# smart_motor_controller.net
KiCad netlist of a schematic drawn in EAGLE
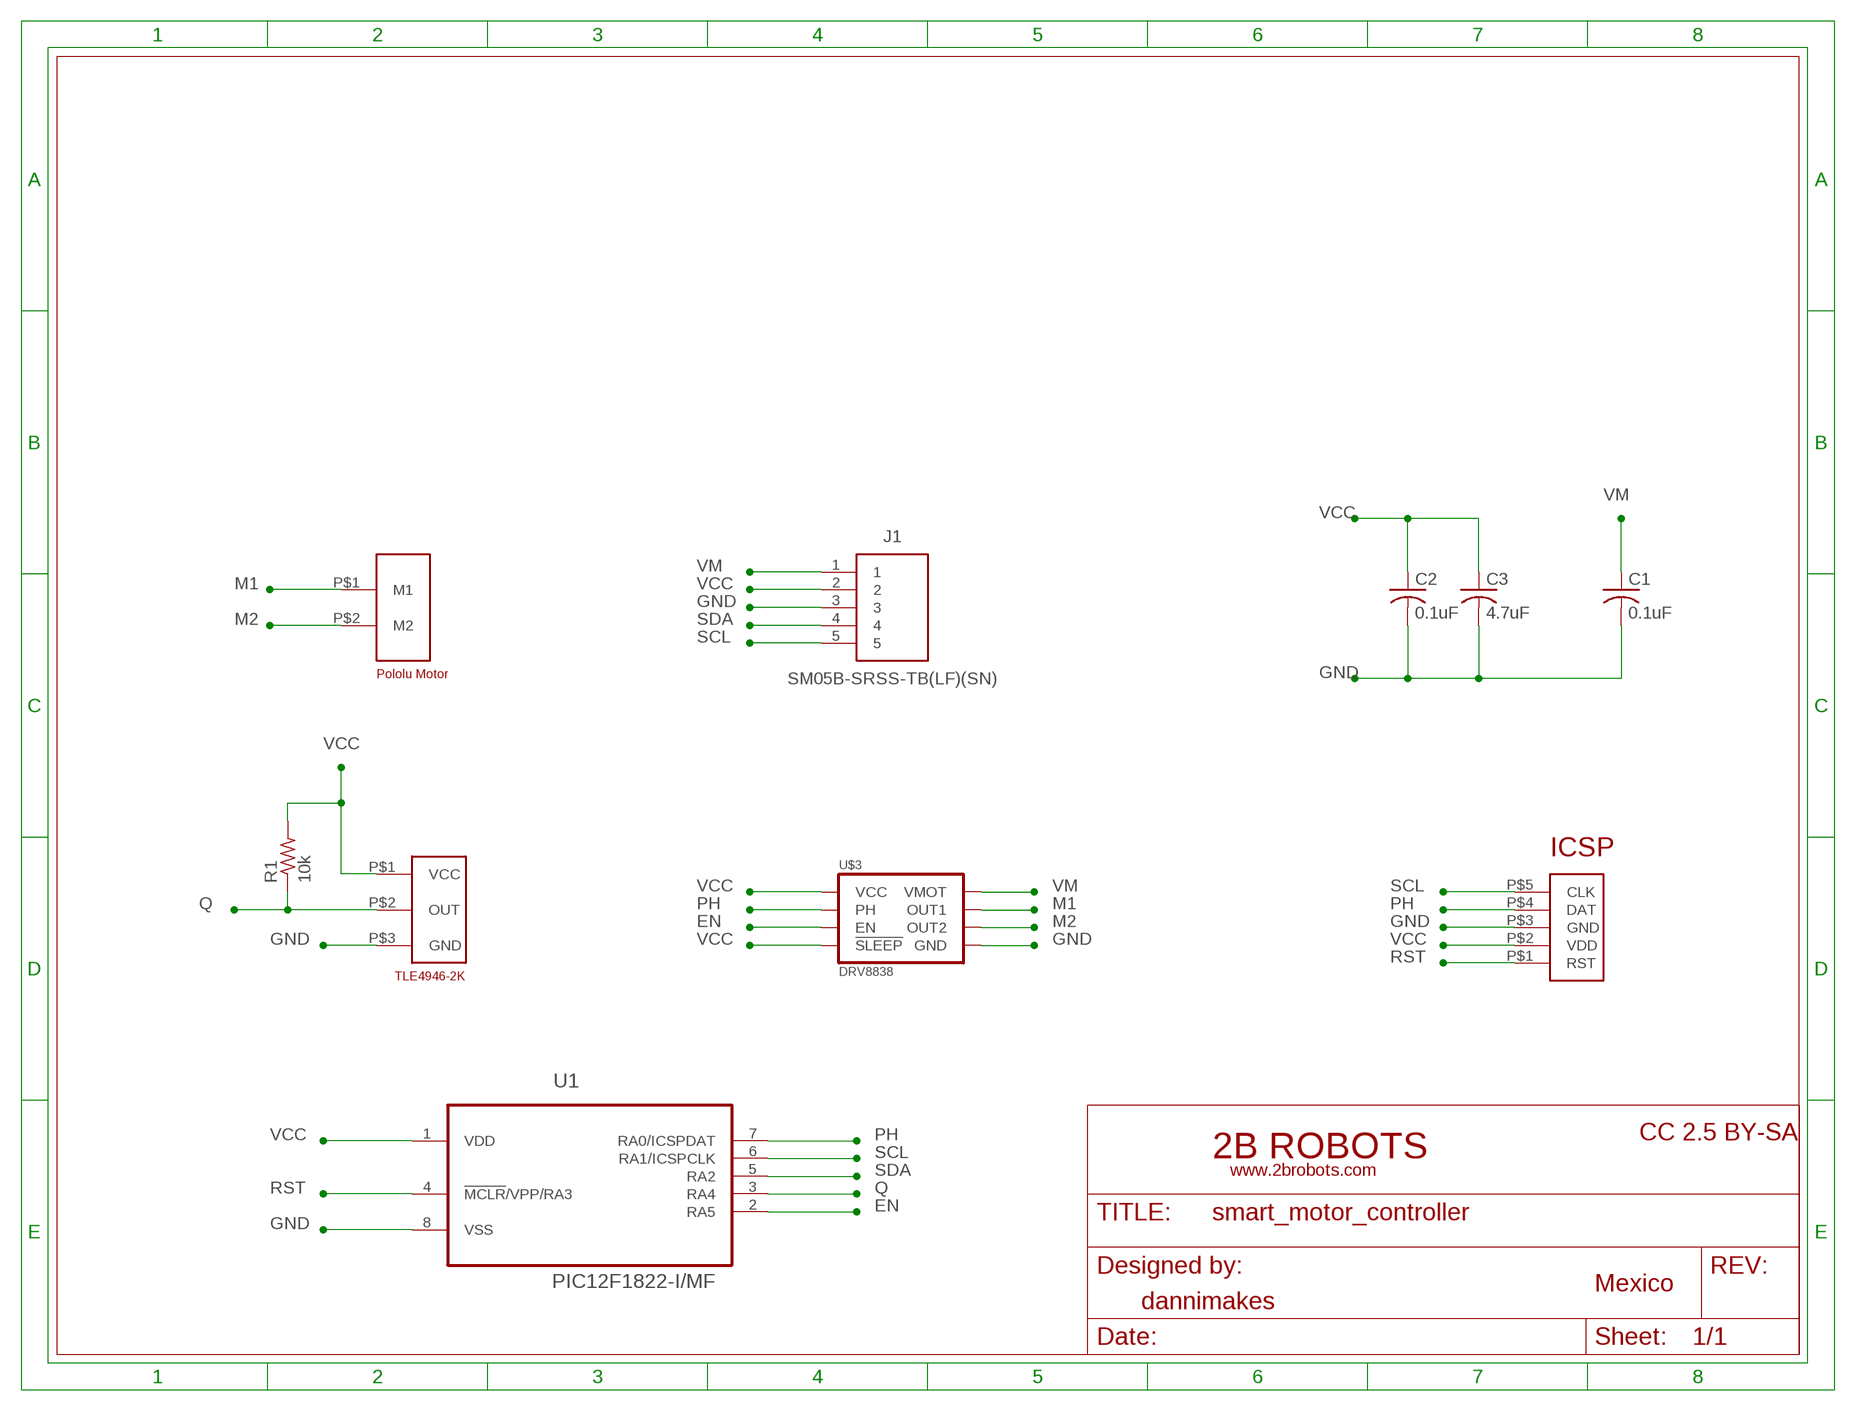
[diagram p0: schematic, sheet 1]

(export (version "E")
  (design (tool "Eeschema 10.0.6"))
  (components
    (comp (ref "C1")
      (value "0.1uF")
      (footprint "eagle-import:C0603K")
      (libsource (lib "eagle-import") (part "C-USC0603K"))
    )
    (comp (ref "C2")
      (value "0.1uF")
      (footprint "eagle-import:C0603K")
      (libsource (lib "eagle-import") (part "C-USC0603K"))
    )
    (comp (ref "C3")
      (value "4.7uF")
      (footprint "eagle-import:C0805K")
      (libsource (lib "eagle-import") (part "C-USC0805K"))
    )
    (comp (ref "J1")
      (value "SM05B-SRSS-TB(LF)(SN)")
      (footprint "eagle-import:SM05B-SRSS-TB(LF)(SN)")
      (libsource (lib "eagle-import") (part "SM05B-SRSS-TB(LF)(SN)"))
    )
    (comp (ref "R1")
      (value "10k")
      (footprint "eagle-import:R0805")
      (libsource (lib "eagle-import") (part "R-US_R0805"))
    )
    (comp (ref "U$1")
      (value "ICSP_POGO")
      (footprint "eagle-import:ICSP_POGO")
      (libsource (lib "eagle-import") (part "ICSP_POGO"))
    )
    (comp (ref "U$3")
      (value "DRV8838")
      (footprint "eagle-import:DSG")
      (libsource (lib "eagle-import") (part "DRV8838"))
    )
    (comp (ref "U$4")
      (value "TLE4946-2K")
      (footprint "eagle-import:SC59")
      (libsource (lib "eagle-import") (part "TLE4946-2K"))
    )
    (comp (ref "U$5")
      (value "POLOLU-MOTOR-BACK")
      (footprint "eagle-import:POLOL-MOTOR-BACK")
      (libsource (lib "eagle-import") (part "POLOLU-MOTOR-BACK"))
    )
    (comp (ref "U1")
      (value "PIC12F1822-I/MF")
      (footprint "eagle-import:DFN300X300X100-9N")
      (libsource (lib "eagle-import") (part "PIC12F1822-I/MF"))
    )
  )
  (nets
    (net (code "1") (name "/EN") (class "Default")
      (node (ref "U$3") (pin "5") (pinfunction "EN_5") (pintype "bidirectional"))
      (node (ref "U1") (pin "2") (pinfunction "RA5_2") (pintype "bidirectional"))
    )
    (net (code "2") (name "/GND") (class "Default")
      (node (ref "C1") (pin "2") (pinfunction "2_2") (pintype "passive"))
      (node (ref "C2") (pin "2") (pinfunction "2_2") (pintype "passive"))
      (node (ref "C3") (pin "2") (pinfunction "2_2") (pintype "passive"))
      (node (ref "J1") (pin "3") (pinfunction "3_3") (pintype "passive"))
      (node (ref "U$1") (pin "P$3") (pinfunction "GND_P$3") (pintype "bidirectional"))
      (node (ref "U$3") (pin "4") (pinfunction "GND_4") (pintype "bidirectional"))
      (node (ref "U$3") (pin "PAD") (pinfunction "GND_PAD") (pintype "bidirectional"))
      (node (ref "U$4") (pin "P$3") (pinfunction "GND_P$3") (pintype "power_in"))
      (node (ref "U1") (pin "8") (pinfunction "VSS_8") (pintype "power_in"))
    )
    (net (code "3") (name "/M1") (class "Default")
      (node (ref "U$3") (pin "2") (pinfunction "OUT1_2") (pintype "bidirectional"))
      (node (ref "U$5") (pin "P$1") (pinfunction "M1_P$1") (pintype "bidirectional"))
    )
    (net (code "4") (name "/M2") (class "Default")
      (node (ref "U$3") (pin "3") (pinfunction "OUT2_3") (pintype "bidirectional"))
      (node (ref "U$5") (pin "P$2") (pinfunction "M2_P$2") (pintype "bidirectional"))
    )
    (net (code "5") (name "/PH") (class "Default")
      (node (ref "U$1") (pin "P$4") (pinfunction "DAT_P$4") (pintype "bidirectional"))
      (node (ref "U$3") (pin "6") (pinfunction "PH_6") (pintype "bidirectional"))
      (node (ref "U1") (pin "7") (pinfunction "RA0/ICSPDAT_7") (pintype "bidirectional"))
    )
    (net (code "6") (name "/Q") (class "Default")
      (node (ref "R1") (pin "1") (pinfunction "1_1") (pintype "passive"))
      (node (ref "U$4") (pin "P$2") (pinfunction "OUT_P$2") (pintype "bidirectional"))
      (node (ref "U1") (pin "3") (pinfunction "RA4_3") (pintype "bidirectional"))
    )
    (net (code "7") (name "/RST") (class "Default")
      (node (ref "U$1") (pin "P$1") (pinfunction "RST_P$1") (pintype "bidirectional"))
      (node (ref "U1") (pin "4") (pinfunction "~{MCLR}/VPP/RA3_4") (pintype "input"))
    )
    (net (code "8") (name "/SCL") (class "Default")
      (node (ref "J1") (pin "5") (pinfunction "5_5") (pintype "passive"))
      (node (ref "U$1") (pin "P$5") (pinfunction "CLK_P$5") (pintype "bidirectional"))
      (node (ref "U1") (pin "6") (pinfunction "RA1/ICSPCLK_6") (pintype "bidirectional"))
    )
    (net (code "9") (name "/SDA") (class "Default")
      (node (ref "J1") (pin "4") (pinfunction "4_4") (pintype "passive"))
      (node (ref "U1") (pin "5") (pinfunction "RA2_5") (pintype "bidirectional"))
    )
    (net (code "10") (name "/VCC") (class "Default")
      (node (ref "C2") (pin "1") (pinfunction "1_1") (pintype "passive"))
      (node (ref "C3") (pin "1") (pinfunction "1_1") (pintype "passive"))
      (node (ref "J1") (pin "2") (pinfunction "2_2") (pintype "passive"))
      (node (ref "R1") (pin "2") (pinfunction "2_2") (pintype "passive"))
      (node (ref "U$1") (pin "P$2") (pinfunction "VDD_P$2") (pintype "bidirectional"))
      (node (ref "U$3") (pin "7") (pinfunction "~{SLEEP}_7") (pintype "bidirectional"))
      (node (ref "U$3") (pin "8") (pinfunction "VCC_8") (pintype "bidirectional"))
      (node (ref "U$4") (pin "P$1") (pinfunction "VCC_P$1") (pintype "power_in"))
      (node (ref "U1") (pin "1") (pinfunction "VDD_1") (pintype "power_in"))
    )
    (net (code "11") (name "/VM") (class "Default")
      (node (ref "C1") (pin "1") (pinfunction "1_1") (pintype "passive"))
      (node (ref "J1") (pin "1") (pinfunction "1_1") (pintype "passive"))
      (node (ref "U$3") (pin "1") (pinfunction "VMOT_1") (pintype "bidirectional"))
    )
  )
)
